# dual_power_supply1.net
KiCad netlist of a schematic drawn in EAGLE
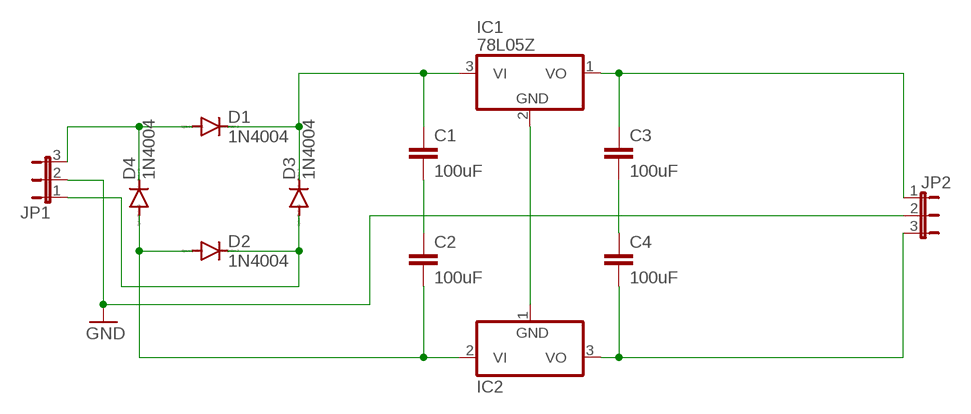
[diagram p0: schematic, sheet 1]

(export (version "E")
  (design (tool "Eeschema 10.0.6"))
  (components
    (comp (ref "C1")
      (value "100uF")
      (footprint "eagle-import:C2.5-2")
      (libsource (lib "eagle-import") (part "C2.5/2"))
    )
    (comp (ref "C2")
      (value "100uF")
      (footprint "eagle-import:C2.5-2")
      (libsource (lib "eagle-import") (part "C2.5/2"))
    )
    (comp (ref "C3")
      (value "100uF")
      (footprint "eagle-import:C2.5-2")
      (libsource (lib "eagle-import") (part "C2.5/2"))
    )
    (comp (ref "C4")
      (value "100uF")
      (footprint "eagle-import:C2.5-2")
      (libsource (lib "eagle-import") (part "C2.5/2"))
    )
    (comp (ref "D1")
      (value "1N4004")
      (footprint "eagle-import:DO41-10")
      (libsource (lib "eagle-import") (part "1N4004"))
    )
    (comp (ref "D2")
      (value "1N4004")
      (footprint "eagle-import:DO41-10")
      (libsource (lib "eagle-import") (part "1N4004"))
    )
    (comp (ref "D3")
      (value "1N4004")
      (footprint "eagle-import:DO41-10")
      (libsource (lib "eagle-import") (part "1N4004"))
    )
    (comp (ref "D4")
      (value "1N4004")
      (footprint "eagle-import:DO41-10")
      (libsource (lib "eagle-import") (part "1N4004"))
    )
    (comp (ref "IC1")
      (value "78L05Z")
      (footprint "eagle-import:TO92")
      (libsource (lib "eagle-import") (part "78ZL05"))
    )
    (comp (ref "IC2")
      (value "7905L")
      (footprint "eagle-import:TO92")
      (libsource (lib "eagle-import") (part "79L05"))
    )
    (comp (ref "JP1")
      (value "JP2E")
      (footprint "eagle-import:JP2")
      (libsource (lib "eagle-import") (part "JP2E"))
    )
    (comp (ref "JP2")
      (value "JP2E")
      (footprint "eagle-import:JP2")
      (libsource (lib "eagle-import") (part "JP2E"))
    )
  )
  (nets
    (net (code "1") (name "GND") (class "Default")
      (node (ref "JP1") (pin "2") (pinfunction "2_2") (pintype "passive"))
      (node (ref "JP2") (pin "2") (pinfunction "2_2") (pintype "passive"))
    )
    (net (code "2") (name "Net-(C1-Pad2)") (class "Default")
      (node (ref "C1") (pin "2") (pinfunction "2_2") (pintype "passive"))
      (node (ref "C2") (pin "1") (pinfunction "1_1") (pintype "passive"))
    )
    (net (code "3") (name "Net-(C3-Pad2)") (class "Default")
      (node (ref "C3") (pin "2") (pinfunction "2_2") (pintype "passive"))
      (node (ref "C4") (pin "1") (pinfunction "1_1") (pintype "passive"))
    )
    (net (code "4") (name "Net-(D1-PadA)") (class "Default")
      (node (ref "D1") (pin "A") (pinfunction "A_A") (pintype "passive"))
      (node (ref "D4") (pin "C") (pinfunction "C_C") (pintype "passive"))
      (node (ref "JP1") (pin "3") (pinfunction "3_3") (pintype "passive"))
    )
    (net (code "5") (name "Net-(D2-PadC)") (class "Default")
      (node (ref "D2") (pin "C") (pinfunction "C_C") (pintype "passive"))
      (node (ref "D3") (pin "A") (pinfunction "A_A") (pintype "passive"))
      (node (ref "JP1") (pin "1") (pinfunction "1_1") (pintype "passive"))
    )
    (net (code "6") (name "Net-(IC1-GND)") (class "Default")
      (node (ref "IC1") (pin "2") (pinfunction "GND_2") (pintype "passive"))
      (node (ref "IC2") (pin "1") (pinfunction "GND_1") (pintype "passive"))
    )
    (net (code "7") (name "Net-(IC1-VI)") (class "Default")
      (node (ref "C1") (pin "1") (pinfunction "1_1") (pintype "passive"))
      (node (ref "D1") (pin "C") (pinfunction "C_C") (pintype "passive"))
      (node (ref "D3") (pin "C") (pinfunction "C_C") (pintype "passive"))
      (node (ref "IC1") (pin "3") (pinfunction "VI_3") (pintype "input"))
    )
    (net (code "8") (name "Net-(IC1-VO)") (class "Default")
      (node (ref "C3") (pin "1") (pinfunction "1_1") (pintype "passive"))
      (node (ref "IC1") (pin "1") (pinfunction "VO_1") (pintype "passive"))
      (node (ref "JP2") (pin "1") (pinfunction "1_1") (pintype "passive"))
    )
    (net (code "9") (name "Net-(IC2-VI)") (class "Default")
      (node (ref "C2") (pin "2") (pinfunction "2_2") (pintype "passive"))
      (node (ref "D2") (pin "A") (pinfunction "A_A") (pintype "passive"))
      (node (ref "D4") (pin "A") (pinfunction "A_A") (pintype "passive"))
      (node (ref "IC2") (pin "2") (pinfunction "VI_2") (pintype "input"))
    )
    (net (code "10") (name "Net-(IC2-VO)") (class "Default")
      (node (ref "C4") (pin "2") (pinfunction "2_2") (pintype "passive"))
      (node (ref "IC2") (pin "3") (pinfunction "VO_3") (pintype "passive"))
      (node (ref "JP2") (pin "3") (pinfunction "3_3") (pintype "passive"))
    )
  )
)
